# finger_jlink_r1_3b.net
KiCad netlist of a schematic drawn in EAGLE
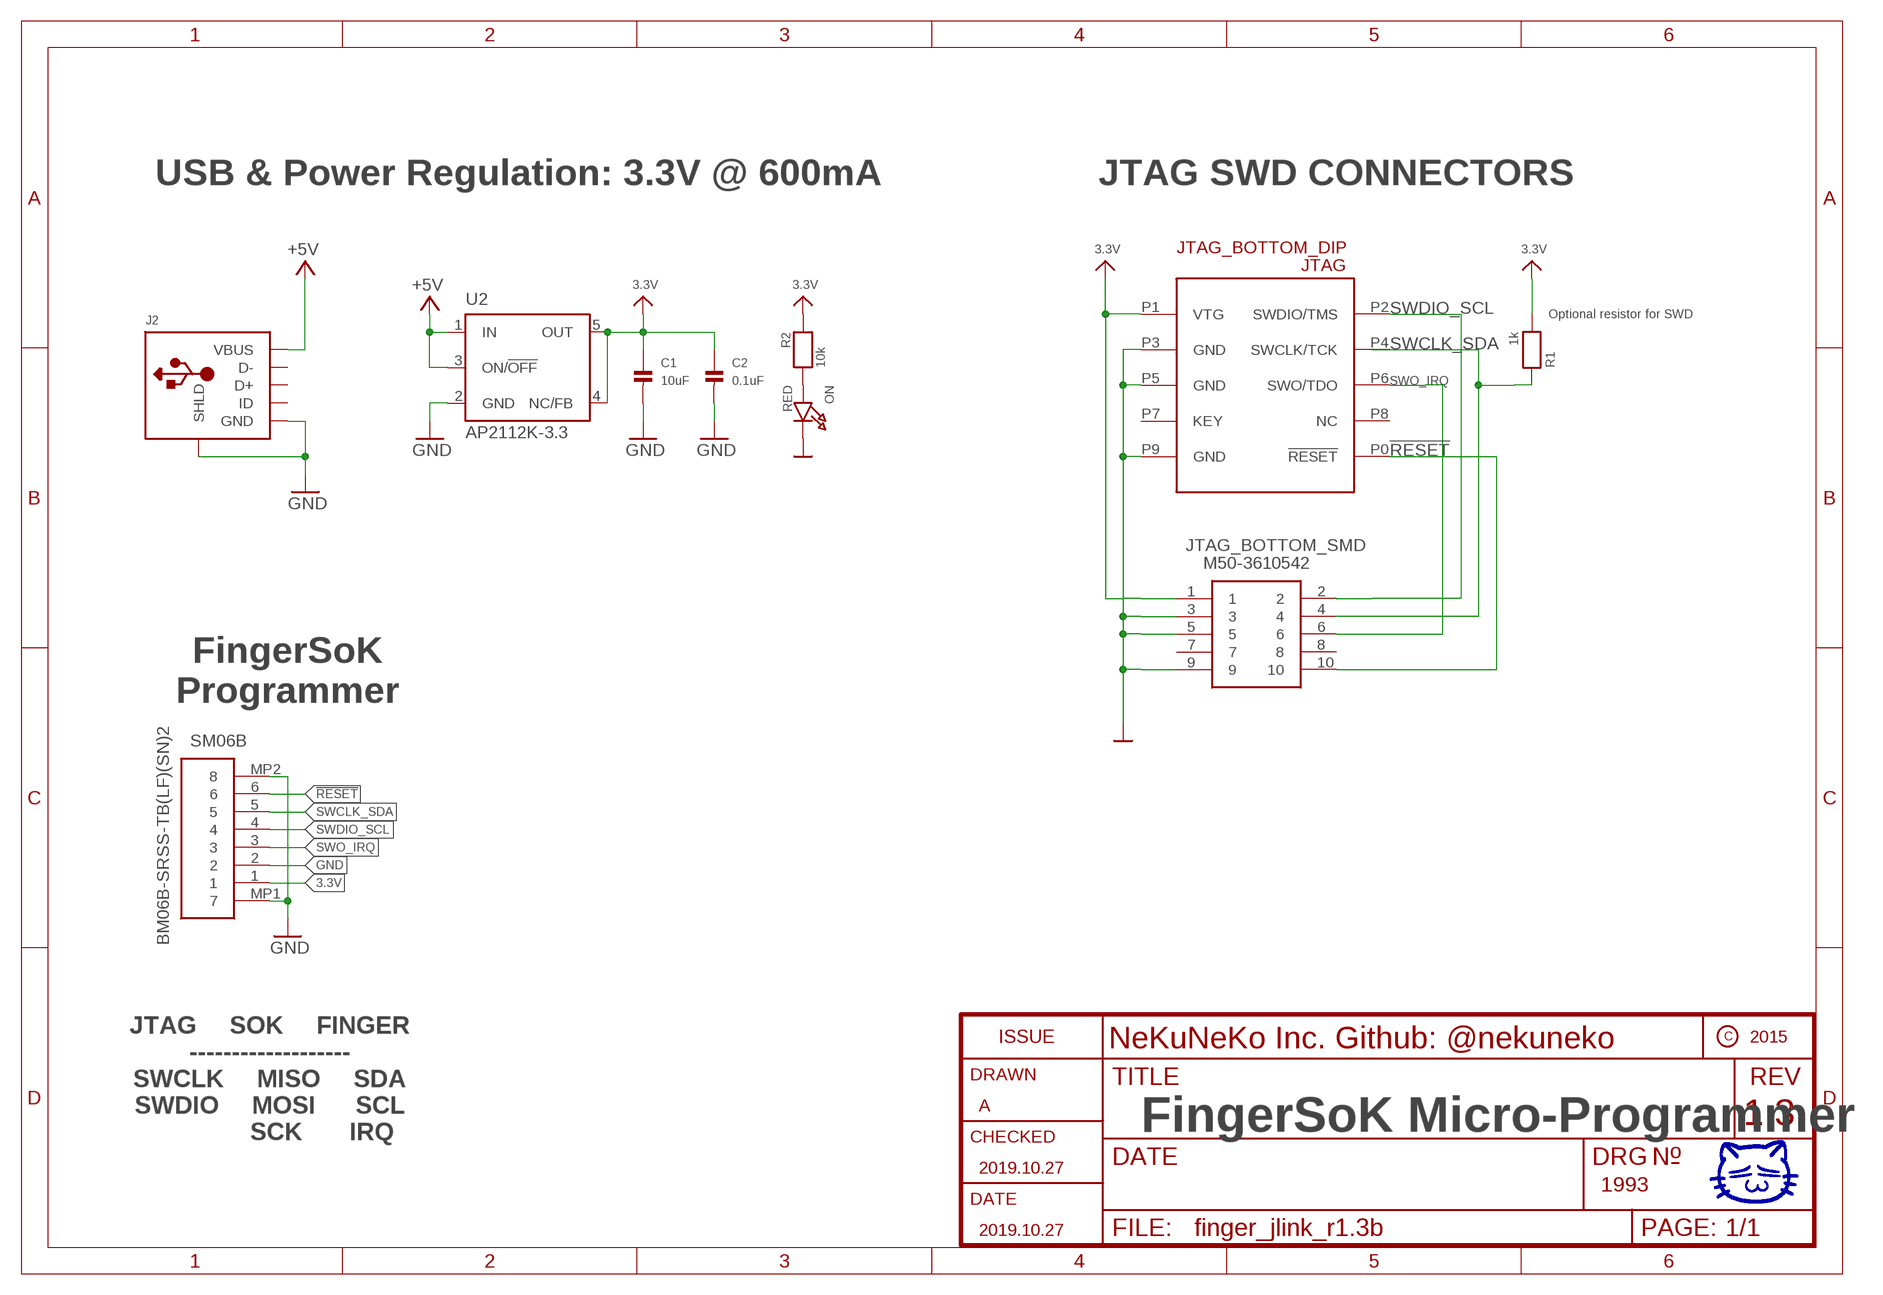
[diagram p0: schematic, sheet 1]

(export (version "E")
  (design (tool "Eeschema 10.0.6"))
  (components
    (comp (ref "C1")
      (value "10uF")
      (footprint "eagle-import:_0402")
      (libsource (lib "eagle-import") (part "CAP_CERAMIC_0402"))
    )
    (comp (ref "C2")
      (value "0.1uF")
      (footprint "eagle-import:_0402")
      (libsource (lib "eagle-import") (part "CAP_CERAMIC_0402"))
    )
    (comp (ref "J2")
      (value "FLAT_MICROUSB_ALIEXPRESS_TYPE_4")
      (footprint "eagle-import:USB_TYPE_4_105164-0001")
      (libsource (lib "eagle-import") (part "FLAT_MICROUSB_ALIEXPRESS_TYPE_4"))
    )
    (comp (ref "JTAG_BOTTOM_DIP")
      (value "JTAGICE3-CONNECTOR50MIL-THT")
      (footprint "eagle-import:JTAGICE3-50MIL")
      (libsource (lib "eagle-import") (part "JTAGICE3-CONNECTOR50MIL-THT"))
    )
    (comp (ref "JTAG_BOTTOM_SMD")
      (value "M50-3610542")
      (footprint "eagle-import:M503610542")
      (fields (field (name "MOUSER_PART_NUMBER") "855-M50-3610542"))
      (libsource (lib "eagle-import") (part "M50-3610542"))
    )
    (comp (ref "ON")
      (value "RED")
      (footprint "eagle-import:CHIPLED_0603")
      (libsource (lib "eagle-import") (part "LED0603"))
    )
    (comp (ref "R1")
      (value "1k")
      (footprint "eagle-import:_0402")
      (libsource (lib "eagle-import") (part "RESISTOR_0402"))
    )
    (comp (ref "R2")
      (value "10k")
      (footprint "eagle-import:_0402")
      (libsource (lib "eagle-import") (part "RESISTOR_0402"))
    )
    (comp (ref "SM06B")
      (value "BM06B-SRSS-TB(LF)(SN)2")
      (footprint "eagle-import:BM06B-SRSS-TB(LF)(SN)_2")
      (libsource (lib "eagle-import") (part "BM06B-SRSS-TB(LF)(SN)2"))
    )
    (comp (ref "U2")
      (value "AP2112K-3.3")
      (footprint "eagle-import:SOT23-DBV")
      (libsource (lib "eagle-import") (part "LP2985-XXDBVR33"))
    )
  )
  (nets
    (net (code "1") (name "+5V") (class "Default")
      (node (ref "J2") (pin "P$5") (pinfunction "VBUS_P$5") (pintype "power_in"))
      (node (ref "U2") (pin "1") (pinfunction "IN_1") (pintype "input"))
      (node (ref "U2") (pin "3") (pinfunction "ON/~{OFF}_3") (pintype "input"))
    )
    (net (code "2") (name "/~{RESET}") (class "Default")
      (node (ref "JTAG_BOTTOM_DIP") (pin "P0") (pinfunction "~{RESET}_P0") (pintype "bidirectional"))
      (node (ref "JTAG_BOTTOM_SMD") (pin "10") (pinfunction "10_10") (pintype "bidirectional"))
      (node (ref "SM06B") (pin "6") (pinfunction "6_6") (pintype "bidirectional"))
    )
    (net (code "3") (name "3.3V") (class "Default")
      (node (ref "C1") (pin "1") (pinfunction "P$1_1") (pintype "passive"))
      (node (ref "C2") (pin "1") (pinfunction "P$1_1") (pintype "passive"))
      (node (ref "JTAG_BOTTOM_DIP") (pin "P1") (pinfunction "VTG_P1") (pintype "bidirectional"))
      (node (ref "JTAG_BOTTOM_SMD") (pin "1") (pinfunction "1_1") (pintype "bidirectional"))
      (node (ref "R1") (pin "2") (pinfunction "2_2") (pintype "passive"))
      (node (ref "R2") (pin "2") (pinfunction "2_2") (pintype "passive"))
      (node (ref "SM06B") (pin "1") (pinfunction "1_1") (pintype "bidirectional"))
      (node (ref "U2") (pin "4") (pinfunction "NC/FB_4") (pintype "passive"))
      (node (ref "U2") (pin "5") (pinfunction "OUT_5") (pintype "passive"))
    )
    (net (code "4") (name "GND") (class "Default")
      (node (ref "C1") (pin "2") (pinfunction "P$2_2") (pintype "passive"))
      (node (ref "C2") (pin "2") (pinfunction "P$2_2") (pintype "passive"))
      (node (ref "J2") (pin "P$1") (pinfunction "GND_P$1") (pintype "power_in"))
      (node (ref "J2") (pin "P$8") (pinfunction "SHLD_P$8") (pintype "power_in"))
      (node (ref "J2") (pin "P$9") (pinfunction "SHLD_P$9") (pintype "power_in"))
      (node (ref "JTAG_BOTTOM_DIP") (pin "P3") (pinfunction "GND_P3") (pintype "bidirectional"))
      (node (ref "JTAG_BOTTOM_DIP") (pin "P5") (pinfunction "GND_P5") (pintype "bidirectional"))
      (node (ref "JTAG_BOTTOM_DIP") (pin "P9") (pinfunction "GND_P9") (pintype "bidirectional"))
      (node (ref "JTAG_BOTTOM_SMD") (pin "3") (pinfunction "3_3") (pintype "bidirectional"))
      (node (ref "JTAG_BOTTOM_SMD") (pin "5") (pinfunction "5_5") (pintype "bidirectional"))
      (node (ref "JTAG_BOTTOM_SMD") (pin "9") (pinfunction "9_9") (pintype "bidirectional"))
      (node (ref "ON") (pin "C") (pinfunction "C_C") (pintype "passive"))
      (node (ref "SM06B") (pin "2") (pinfunction "2_2") (pintype "bidirectional"))
      (node (ref "SM06B") (pin "MP1") (pinfunction "7_MP1") (pintype "bidirectional"))
      (node (ref "SM06B") (pin "MP2") (pinfunction "8_MP2") (pintype "bidirectional"))
      (node (ref "U2") (pin "2") (pinfunction "GND_2") (pintype "power_in"))
    )
    (net (code "5") (name "Net-(ON-PadA)") (class "Default")
      (node (ref "ON") (pin "A") (pinfunction "A_A") (pintype "passive"))
      (node (ref "R2") (pin "1") (pinfunction "1_1") (pintype "passive"))
    )
    (net (code "6") (name "SWCLK_SDA") (class "Default")
      (node (ref "JTAG_BOTTOM_DIP") (pin "P4") (pinfunction "SWCLK/TCK_P4") (pintype "bidirectional"))
      (node (ref "JTAG_BOTTOM_SMD") (pin "4") (pinfunction "4_4") (pintype "bidirectional"))
      (node (ref "R1") (pin "1") (pinfunction "1_1") (pintype "passive"))
      (node (ref "SM06B") (pin "5") (pinfunction "5_5") (pintype "bidirectional"))
    )
    (net (code "7") (name "SWDIO_SCL") (class "Default")
      (node (ref "JTAG_BOTTOM_DIP") (pin "P2") (pinfunction "SWDIO/TMS_P2") (pintype "bidirectional"))
      (node (ref "JTAG_BOTTOM_SMD") (pin "2") (pinfunction "2_2") (pintype "bidirectional"))
      (node (ref "SM06B") (pin "4") (pinfunction "4_4") (pintype "bidirectional"))
    )
    (net (code "8") (name "SWO_IRQ") (class "Default")
      (node (ref "JTAG_BOTTOM_DIP") (pin "P6") (pinfunction "SWO/TDO_P6") (pintype "bidirectional"))
      (node (ref "JTAG_BOTTOM_SMD") (pin "6") (pinfunction "6_6") (pintype "bidirectional"))
      (node (ref "SM06B") (pin "3") (pinfunction "3_3") (pintype "bidirectional"))
    )
    (net (code "9") (name "unconnected-(J2-D+-PadP$3)") (class "Default")
      (node (ref "J2") (pin "P$3") (pinfunction "D+_P$3") (pintype "bidirectional"))
    )
    (net (code "10") (name "unconnected-(J2-D--PadP$4)") (class "Default")
      (node (ref "J2") (pin "P$4") (pinfunction "D-_P$4") (pintype "bidirectional"))
    )
    (net (code "11") (name "unconnected-(J2-ID-PadP$2)") (class "Default")
      (node (ref "J2") (pin "P$2") (pinfunction "ID_P$2") (pintype "bidirectional"))
    )
    (net (code "12") (name "unconnected-(JTAG_BOTTOM_DIP-KEY-PadP7)") (class "Default")
      (node (ref "JTAG_BOTTOM_DIP") (pin "P7") (pinfunction "KEY_P7") (pintype "bidirectional"))
    )
    (net (code "13") (name "unconnected-(JTAG_BOTTOM_DIP-NC-PadP8)") (class "Default")
      (node (ref "JTAG_BOTTOM_DIP") (pin "P8") (pinfunction "NC_P8") (pintype "bidirectional"))
    )
    (net (code "14") (name "unconnected-(JTAG_BOTTOM_SMD-Pad7)") (class "Default")
      (node (ref "JTAG_BOTTOM_SMD") (pin "7") (pinfunction "7_7") (pintype "bidirectional"))
    )
    (net (code "15") (name "unconnected-(JTAG_BOTTOM_SMD-Pad8)") (class "Default")
      (node (ref "JTAG_BOTTOM_SMD") (pin "8") (pinfunction "8_8") (pintype "bidirectional"))
    )
  )
)
